# Main.net
KiCad netlist of a schematic drawn in EAGLE
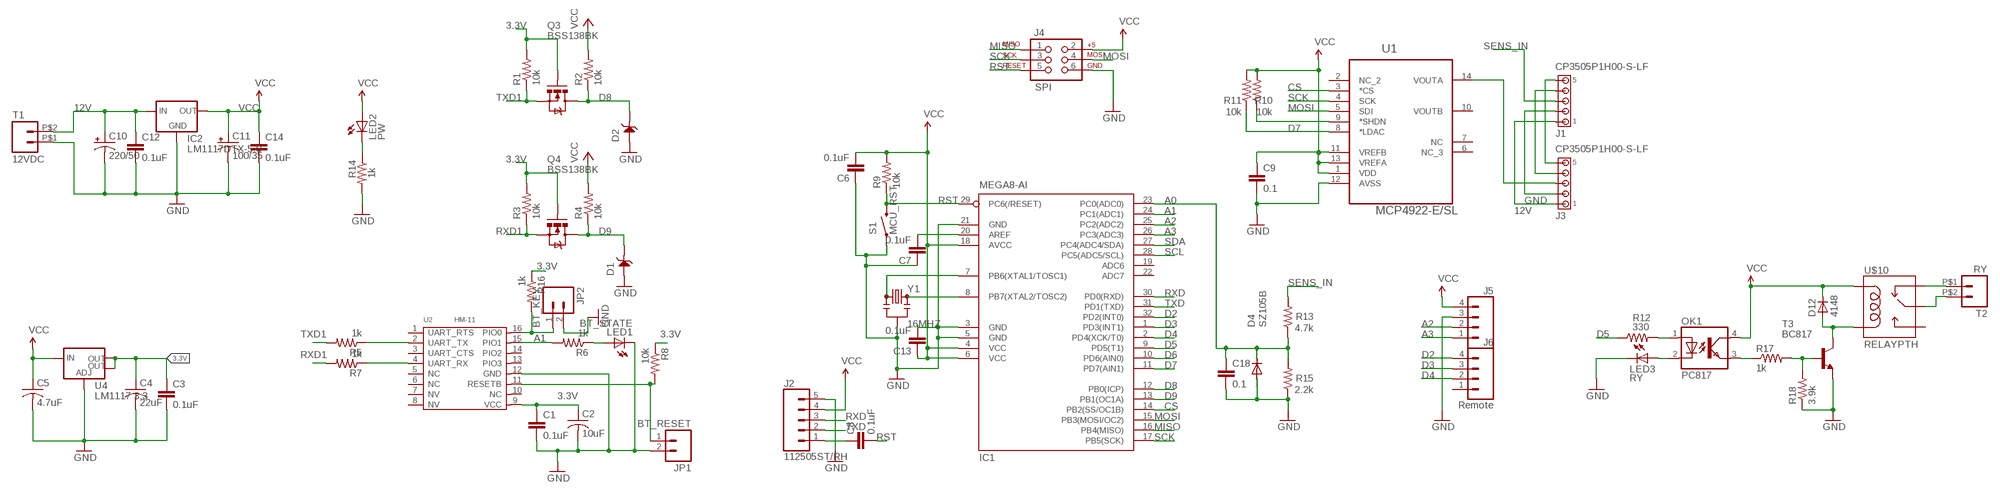
[diagram p0: schematic, sheet 1]

(export (version "E")
  (design (tool "Eeschema 10.0.6"))
  (components
    (comp (ref "C1")
      (value "0.1uF")
      (footprint "eagle-import:0805")
      (libsource (lib "eagle-import") (part "CAP0805"))
    )
    (comp (ref "C2")
      (value "10uF")
      (footprint "eagle-import:C1206")
      (libsource (lib "eagle-import") (part "C-USC1206"))
    )
    (comp (ref "C3")
      (value "0.1uF")
      (footprint "eagle-import:0805")
      (libsource (lib "eagle-import") (part "SparkFun-Passives_CAP0805"))
    )
    (comp (ref "C4")
      (value "22uF")
      (footprint "eagle-import:C1206")
      (libsource (lib "eagle-import") (part "C-USC1206"))
    )
    (comp (ref "C5")
      (value "4.7uF")
      (footprint "eagle-import:C1206")
      (libsource (lib "eagle-import") (part "C-USC1206"))
    )
    (comp (ref "C6")
      (value "0.1uF")
      (footprint "eagle-import:0805")
      (libsource (lib "eagle-import") (part "SparkFun-Passives_CAP0805"))
    )
    (comp (ref "C7")
      (value "0.1uF")
      (footprint "eagle-import:0805")
      (libsource (lib "eagle-import") (part "SparkFun-Passives_CAP0805"))
    )
    (comp (ref "C8")
      (value "0.1uF")
      (footprint "eagle-import:0805")
      (libsource (lib "eagle-import") (part "SparkFun-Passives_CAP0805"))
    )
    (comp (ref "C9")
      (value "0.1")
      (footprint "eagle-import:0805")
      (libsource (lib "eagle-import") (part "SparkFun-Passives_CAP0805"))
    )
    (comp (ref "C10")
      (value "220/50")
      (footprint "eagle-import:153CLV-1010")
      (libsource (lib "eagle-import") (part "CPOL-US153CLV-1010"))
    )
    (comp (ref "C11")
      (value "100/35")
      (footprint "eagle-import:153CLV-0605")
      (libsource (lib "eagle-import") (part "CPOL-US153CLV-0605"))
    )
    (comp (ref "C12")
      (value "0.1uF")
      (footprint "eagle-import:0805")
      (libsource (lib "eagle-import") (part "SparkFun-Passives_CAP0805"))
    )
    (comp (ref "C13")
      (value "0.1uF")
      (footprint "eagle-import:0805")
      (libsource (lib "eagle-import") (part "SparkFun-Passives_CAP0805"))
    )
    (comp (ref "C14")
      (value "0.1uF")
      (footprint "eagle-import:0805")
      (libsource (lib "eagle-import") (part "SparkFun-Passives_CAP0805"))
    )
    (comp (ref "C18")
      (value "0.1")
      (footprint "eagle-import:0805")
      (libsource (lib "eagle-import") (part "SparkFun-Passives_CAP0805"))
    )
    (comp (ref "D1")
      (value "SMF5.0A")
      (footprint "eagle-import:SOD123-2.7X1.6")
      (libsource (lib "eagle-import") (part "D-ESD-2P'CESD5V0D1'"))
    )
    (comp (ref "D2")
      (value "SMF5.0A")
      (footprint "eagle-import:SOD123-2.7X1.6")
      (libsource (lib "eagle-import") (part "D-ESD-2P'CESD5V0D1'"))
    )
    (comp (ref "D4")
      (value "SZ105B")
      (footprint "eagle-import:DO-214AC")
      (libsource (lib "eagle-import") (part "DIODE-DO-214AC"))
    )
    (comp (ref "D12")
      (value "4148")
      (footprint "eagle-import:SOD80")
      (libsource (lib "eagle-import") (part "D-SOD-80"))
    )
    (comp (ref "IC1")
      (value "MEGA8-AI")
      (footprint "eagle-import:TQFP32-08")
      (fields (field (name "MPN") "ATMEGA8-16AU"))
      (libsource (lib "eagle-import") (part "MEGA8-AI"))
    )
    (comp (ref "IC2")
      (value "LM1117DTX-5.0")
      (footprint "eagle-import:TO252")
      (libsource (lib "eagle-import") (part "LM1117DTX-3.3"))
    )
    (comp (ref "J1")
      (value "CP3505P1H00-S-LF")
      (footprint "eagle-import:1445055-5")
      (libsource (lib "eagle-import") (part "1445055-5"))
    )
    (comp (ref "J2")
      (value "112505ST/RH")
      (footprint "eagle-import:JST-5-PTH")
      (libsource (lib "eagle-import") (part "CONN_05JST"))
    )
    (comp (ref "J3")
      (value "CP3505P1H00-S-LF")
      (footprint "eagle-import:1445055-5")
      (libsource (lib "eagle-import") (part "1445055-5"))
    )
    (comp (ref "J4")
      (value "SPI")
      (footprint "eagle-import:2X3")
      (libsource (lib "eagle-import") (part "AVR_SPI_PRG_6PTH"))
    )
    (comp (ref "J5")
      (value "CONN_04JST-PTH")
      (footprint "eagle-import:JST-4-PTH")
      (libsource (lib "eagle-import") (part "CONN_04JST-PTH"))
    )
    (comp (ref "J6")
      (value "Remote")
      (footprint "eagle-import:JST-4-PTH")
      (libsource (lib "eagle-import") (part "CONN_04JST-PTH"))
    )
    (comp (ref "JP1")
      (value "BT_RESET")
      (footprint "eagle-import:1X02")
      (libsource (lib "eagle-import") (part "M02PTH"))
    )
    (comp (ref "JP2")
      (value "BT_KEY")
      (footprint "eagle-import:1X02")
      (libsource (lib "eagle-import") (part "M02PTH"))
    )
    (comp (ref "LED1")
      (value "BT_STATE")
      (footprint "eagle-import:LED3MM")
      (libsource (lib "eagle-import") (part "LED3MM"))
    )
    (comp (ref "LED2")
      (value "PW")
      (footprint "eagle-import:LED3MM")
      (libsource (lib "eagle-import") (part "LED3MM"))
    )
    (comp (ref "LED3")
      (value "RY")
      (footprint "eagle-import:LED3MM")
      (libsource (lib "eagle-import") (part "LED3MM"))
    )
    (comp (ref "OK1")
      (value "PC817")
      (footprint "eagle-import:DIL4-SMD")
      (libsource (lib "eagle-import") (part "LTV816S"))
    )
    (comp (ref "Q3")
      (value "BSS138BK")
      (footprint "eagle-import:SOT23-3")
      (libsource (lib "eagle-import") (part "MOSFET-NCHANNELBSS138"))
    )
    (comp (ref "Q4")
      (value "BSS138BK")
      (footprint "eagle-import:SOT23-3")
      (libsource (lib "eagle-import") (part "MOSFET-NCHANNELBSS138"))
    )
    (comp (ref "R1")
      (value "10k")
      (footprint "eagle-import:0805")
      (libsource (lib "eagle-import") (part "SparkFun-Resistors_RESISTOR0805-RES"))
    )
    (comp (ref "R2")
      (value "10k")
      (footprint "eagle-import:0805")
      (libsource (lib "eagle-import") (part "SparkFun-Resistors_RESISTOR0805-RES"))
    )
    (comp (ref "R3")
      (value "10k")
      (footprint "eagle-import:0805")
      (libsource (lib "eagle-import") (part "SparkFun-Resistors_RESISTOR0805-RES"))
    )
    (comp (ref "R4")
      (value "10k")
      (footprint "eagle-import:0805")
      (libsource (lib "eagle-import") (part "SparkFun-Resistors_RESISTOR0805-RES"))
    )
    (comp (ref "R5")
      (value "1k")
      (footprint "eagle-import:0805")
      (libsource (lib "eagle-import") (part "SparkFun-Resistors_RESISTOR0805-RES"))
    )
    (comp (ref "R6")
      (value "1k")
      (footprint "eagle-import:0805")
      (libsource (lib "eagle-import") (part "SparkFun-Resistors_RESISTOR0805-RES"))
    )
    (comp (ref "R7")
      (value "1k")
      (footprint "eagle-import:0805")
      (libsource (lib "eagle-import") (part "SparkFun-Resistors_RESISTOR0805-RES"))
    )
    (comp (ref "R8")
      (value "10k")
      (footprint "eagle-import:0805")
      (libsource (lib "eagle-import") (part "SparkFun-Resistors_RESISTOR0805-RES"))
    )
    (comp (ref "R9")
      (value "10k")
      (footprint "eagle-import:0805")
      (libsource (lib "eagle-import") (part "SparkFun-Resistors_RESISTOR0805-RES"))
    )
    (comp (ref "R10")
      (value "10k")
      (footprint "eagle-import:0805")
      (libsource (lib "eagle-import") (part "SparkFun-Resistors_RESISTOR0805-RES"))
    )
    (comp (ref "R11")
      (value "10k")
      (footprint "eagle-import:0805")
      (libsource (lib "eagle-import") (part "SparkFun-Resistors_RESISTOR0805-RES"))
    )
    (comp (ref "R12")
      (value "330")
      (footprint "eagle-import:0805")
      (libsource (lib "eagle-import") (part "RESISTOR0805-RES"))
    )
    (comp (ref "R13")
      (value "4.7k")
      (footprint "eagle-import:0805")
      (libsource (lib "eagle-import") (part "SparkFun-Resistors_RESISTOR0805-RES"))
    )
    (comp (ref "R14")
      (value "1k")
      (footprint "eagle-import:0805")
      (libsource (lib "eagle-import") (part "SparkFun-Resistors_RESISTOR0805-RES"))
    )
    (comp (ref "R15")
      (value "2.2k")
      (footprint "eagle-import:0805")
      (libsource (lib "eagle-import") (part "SparkFun-Resistors_RESISTOR0805-RES"))
    )
    (comp (ref "R16")
      (value "1k")
      (footprint "eagle-import:0805")
      (libsource (lib "eagle-import") (part "SparkFun-Resistors_RESISTOR0805-RES"))
    )
    (comp (ref "R17")
      (value "1k")
      (footprint "eagle-import:0805")
      (libsource (lib "eagle-import") (part "RESISTOR0805-RES"))
    )
    (comp (ref "R18")
      (value "3.9k")
      (footprint "eagle-import:0805")
      (libsource (lib "eagle-import") (part "RESISTOR0805-RES"))
    )
    (comp (ref "S1")
      (value "MCU_RST")
      (footprint "eagle-import:TACTILE-SWITCH-1101NE")
      (libsource (lib "eagle-import") (part "SWITCH-MOMENTARY-2SMD-1101NE"))
    )
    (comp (ref "T1")
      (value "12VDC")
      (footprint "eagle-import:ED350V-02P")
      (libsource (lib "eagle-import") (part "ST02-3.5MM"))
    )
    (comp (ref "T2")
      (value "RY")
      (footprint "eagle-import:ED350V-02P")
      (libsource (lib "eagle-import") (part "ST02-3.5MM"))
    )
    (comp (ref "T3")
      (value "BC817")
      (footprint "eagle-import:SOT23-BEC")
      (libsource (lib "eagle-import") (part "-NPN-SOT23-BECBC817-16"))
    )
    (comp (ref "U$10")
      (value "RELAYPTH")
      (footprint "eagle-import:SRD-05VDC-SL-C")
      (libsource (lib "eagle-import") (part "RELAYPTH"))
    )
    (comp (ref "U1")
      (value "MCP4922-E/SL")
      (footprint "eagle-import:SOIC127P600X175-14N")
      (libsource (lib "eagle-import") (part "MCP4922-E/SL"))
    )
    (comp (ref "U2")
      (value "HM-11")
      (footprint "eagle-import:16P-18.5X13.5X0.8")
      (libsource (lib "eagle-import") (part "HM-11"))
    )
    (comp (ref "U4")
      (value "LM1117 3.3")
      (footprint "eagle-import:SOT223")
      (libsource (lib "eagle-import") (part "V_REG_LM1117SOT223"))
    )
    (comp (ref "Y1")
      (value "16MHZ")
      (footprint "eagle-import:RESONATOR-SMD")
      (libsource (lib "eagle-import") (part "RESONATOR16MHZ"))
    )
  )
  (nets
    (net (code "1") (name "/12V") (class "Default")
      (node (ref "C10") (pin "+") (pinfunction "+_+") (pintype "passive"))
      (node (ref "C12") (pin "1") (pinfunction "1_1") (pintype "passive"))
      (node (ref "IC2") (pin "2") (pinfunction "IN_2") (pintype "input"))
      (node (ref "J1") (pin "1") (pinfunction "1_1") (pintype "passive"))
      (node (ref "J3") (pin "1") (pinfunction "1_1") (pintype "passive"))
      (node (ref "T1") (pin "P$2") (pinfunction "2_P$2") (pintype "passive"))
    )
    (net (code "2") (name "/A0") (class "Default")
      (node (ref "C18") (pin "1") (pinfunction "1_1") (pintype "passive"))
      (node (ref "D4") (pin "C") (pinfunction "C_C") (pintype "passive"))
      (node (ref "IC1") (pin "23") (pinfunction "PC0(ADC0)_23") (pintype "bidirectional"))
      (node (ref "R13") (pin "1") (pinfunction "1_1") (pintype "passive"))
      (node (ref "R15") (pin "2") (pinfunction "2_2") (pintype "passive"))
    )
    (net (code "3") (name "/A1") (class "Default")
      (node (ref "IC1") (pin "24") (pinfunction "PC1(ADC1)_24") (pintype "bidirectional"))
      (node (ref "R6") (pin "2") (pinfunction "2_2") (pintype "passive"))
      (node (ref "U2") (pin "15") (pinfunction "PIO1_15") (pintype "bidirectional"))
    )
    (net (code "4") (name "/A2") (class "Default")
      (node (ref "IC1") (pin "25") (pinfunction "PC2(ADC2)_25") (pintype "bidirectional"))
      (node (ref "J5") (pin "2") (pinfunction "2_2") (pintype "passive"))
    )
    (net (code "5") (name "/A3") (class "Default")
      (node (ref "IC1") (pin "26") (pinfunction "PC3(ADC3)_26") (pintype "bidirectional"))
      (node (ref "J5") (pin "1") (pinfunction "1_1") (pintype "passive"))
    )
    (net (code "6") (name "/CS") (class "Default")
      (node (ref "IC1") (pin "14") (pinfunction "PB2(SS/OC1B)_14") (pintype "bidirectional"))
      (node (ref "U1") (pin "3") (pinfunction "*CS_3") (pintype "input"))
    )
    (net (code "7") (name "/D2") (class "Default")
      (node (ref "IC1") (pin "32") (pinfunction "PD2(INT0)_32") (pintype "bidirectional"))
      (node (ref "J6") (pin "4") (pinfunction "4_4") (pintype "passive"))
    )
    (net (code "8") (name "/D3") (class "Default")
      (node (ref "IC1") (pin "1") (pinfunction "PD3(INT1)_1") (pintype "bidirectional"))
      (node (ref "J6") (pin "3") (pinfunction "3_3") (pintype "passive"))
    )
    (net (code "9") (name "/D4") (class "Default")
      (node (ref "IC1") (pin "2") (pinfunction "PD4(XCK/T0)_2") (pintype "bidirectional"))
      (node (ref "J6") (pin "2") (pinfunction "2_2") (pintype "passive"))
    )
    (net (code "10") (name "/D5") (class "Default")
      (node (ref "IC1") (pin "9") (pinfunction "PD5(T1)_9") (pintype "bidirectional"))
      (node (ref "R12") (pin "1") (pinfunction "1_1") (pintype "passive"))
    )
    (net (code "11") (name "/D6") (class "Default")
      (node (ref "IC1") (pin "10") (pinfunction "PD6(AIN0)_10") (pintype "bidirectional"))
    )
    (net (code "12") (name "/D7") (class "Default")
      (node (ref "IC1") (pin "11") (pinfunction "PD7(AIN1)_11") (pintype "bidirectional"))
      (node (ref "R11") (pin "1") (pinfunction "1_1") (pintype "passive"))
      (node (ref "U1") (pin "8") (pinfunction "*LDAC_8") (pintype "input"))
    )
    (net (code "13") (name "/D8") (class "Default")
      (node (ref "D2") (pin "2") (pinfunction "2_2") (pintype "bidirectional"))
      (node (ref "IC1") (pin "12") (pinfunction "PB0(ICP)_12") (pintype "bidirectional"))
      (node (ref "Q3") (pin "3") (pinfunction "D_3") (pintype "passive"))
      (node (ref "R2") (pin "1") (pinfunction "1_1") (pintype "passive"))
    )
    (net (code "14") (name "/D9") (class "Default")
      (node (ref "D1") (pin "2") (pinfunction "2_2") (pintype "bidirectional"))
      (node (ref "IC1") (pin "13") (pinfunction "PB1(OC1A)_13") (pintype "bidirectional"))
      (node (ref "Q4") (pin "3") (pinfunction "D_3") (pintype "passive"))
      (node (ref "R4") (pin "1") (pinfunction "1_1") (pintype "passive"))
    )
    (net (code "15") (name "/MISO") (class "Default")
      (node (ref "IC1") (pin "16") (pinfunction "PB4(MISO)_16") (pintype "bidirectional"))
      (node (ref "J4") (pin "1") (pinfunction "1_1") (pintype "passive"))
    )
    (net (code "16") (name "/MOSI") (class "Default")
      (node (ref "IC1") (pin "15") (pinfunction "PB3(MOSI/OC2)_15") (pintype "bidirectional"))
      (node (ref "J4") (pin "4") (pinfunction "4_4") (pintype "passive"))
      (node (ref "U1") (pin "5") (pinfunction "SDI_5") (pintype "input"))
    )
    (net (code "17") (name "/RST") (class "Default")
      (node (ref "C8") (pin "2") (pinfunction "2_2") (pintype "passive"))
      (node (ref "IC1") (pin "29") (pinfunction "PC6(/RESET)_29") (pintype "bidirectional"))
      (node (ref "J4") (pin "5") (pinfunction "5_5") (pintype "passive"))
      (node (ref "R9") (pin "1") (pinfunction "1_1") (pintype "passive"))
      (node (ref "S1") (pin "2") (pinfunction "2_2") (pintype "passive"))
    )
    (net (code "18") (name "/RXD") (class "Default")
      (node (ref "IC1") (pin "30") (pinfunction "PD0(RXD)_30") (pintype "bidirectional"))
      (node (ref "J2") (pin "3") (pinfunction "3_3") (pintype "passive"))
    )
    (net (code "19") (name "/RXD1") (class "Default")
      (node (ref "Q4") (pin "2") (pinfunction "S_2") (pintype "passive"))
      (node (ref "R3") (pin "1") (pinfunction "1_1") (pintype "passive"))
      (node (ref "R7") (pin "2") (pinfunction "2_2") (pintype "passive"))
    )
    (net (code "20") (name "/SCK") (class "Default")
      (node (ref "IC1") (pin "17") (pinfunction "PB5(SCK)_17") (pintype "bidirectional"))
      (node (ref "J4") (pin "3") (pinfunction "3_3") (pintype "passive"))
      (node (ref "U1") (pin "4") (pinfunction "SCK_4") (pintype "input"))
    )
    (net (code "21") (name "/SCL") (class "Default")
      (node (ref "IC1") (pin "28") (pinfunction "PC5(ADC5/SCL)_28") (pintype "bidirectional"))
    )
    (net (code "22") (name "/SDA") (class "Default")
      (node (ref "IC1") (pin "27") (pinfunction "PC4(ADC4/SDA)_27") (pintype "bidirectional"))
    )
    (net (code "23") (name "/SENS_IN") (class "Default")
      (node (ref "J1") (pin "3") (pinfunction "3_3") (pintype "passive"))
      (node (ref "R13") (pin "2") (pinfunction "2_2") (pintype "passive"))
    )
    (net (code "24") (name "/TXD") (class "Default")
      (node (ref "IC1") (pin "31") (pinfunction "PD1(TXD)_31") (pintype "bidirectional"))
      (node (ref "J2") (pin "2") (pinfunction "2_2") (pintype "passive"))
    )
    (net (code "25") (name "/TXD1") (class "Default")
      (node (ref "Q3") (pin "2") (pinfunction "S_2") (pintype "passive"))
      (node (ref "R1") (pin "1") (pinfunction "1_1") (pintype "passive"))
      (node (ref "R5") (pin "2") (pinfunction "2_2") (pintype "passive"))
    )
    (net (code "26") (name "3.3V") (class "Default")
      (node (ref "C1") (pin "1") (pinfunction "1_1") (pintype "passive"))
      (node (ref "C2") (pin "1") (pinfunction "1_1") (pintype "passive"))
      (node (ref "C3") (pin "1") (pinfunction "1_1") (pintype "passive"))
      (node (ref "C4") (pin "1") (pinfunction "1_1") (pintype "passive"))
      (node (ref "Q3") (pin "1") (pinfunction "G_1") (pintype "passive"))
      (node (ref "Q4") (pin "1") (pinfunction "G_1") (pintype "passive"))
      (node (ref "R1") (pin "2") (pinfunction "2_2") (pintype "passive"))
      (node (ref "R16") (pin "1") (pinfunction "1_1") (pintype "passive"))
      (node (ref "R3") (pin "2") (pinfunction "2_2") (pintype "passive"))
      (node (ref "R8") (pin "1") (pinfunction "1_1") (pintype "passive"))
      (node (ref "U2") (pin "9") (pinfunction "VCC_9") (pintype "bidirectional"))
      (node (ref "U4") (pin "2") (pinfunction "OUT_2") (pintype "output"))
      (node (ref "U4") (pin "4") (pinfunction "OUT_4") (pintype "output"))
    )
    (net (code "27") (name "GND") (class "Default")
      (node (ref "C1") (pin "2") (pinfunction "2_2") (pintype "passive"))
      (node (ref "C10") (pin "-") (pinfunction "-_-") (pintype "passive"))
      (node (ref "C11") (pin "-") (pinfunction "-_-") (pintype "passive"))
      (node (ref "C12") (pin "2") (pinfunction "2_2") (pintype "passive"))
      (node (ref "C13") (pin "2") (pinfunction "2_2") (pintype "passive"))
      (node (ref "C14") (pin "2") (pinfunction "2_2") (pintype "passive"))
      (node (ref "C18") (pin "2") (pinfunction "2_2") (pintype "passive"))
      (node (ref "C2") (pin "2") (pinfunction "2_2") (pintype "passive"))
      (node (ref "C3") (pin "2") (pinfunction "2_2") (pintype "passive"))
      (node (ref "C4") (pin "2") (pinfunction "2_2") (pintype "passive"))
      (node (ref "C5") (pin "2") (pinfunction "2_2") (pintype "passive"))
      (node (ref "C6") (pin "1") (pinfunction "1_1") (pintype "passive"))
      (node (ref "C7") (pin "1") (pinfunction "1_1") (pintype "passive"))
      (node (ref "C9") (pin "2") (pinfunction "2_2") (pintype "passive"))
      (node (ref "D1") (pin "1") (pinfunction "1_1") (pintype "bidirectional"))
      (node (ref "D2") (pin "1") (pinfunction "1_1") (pintype "bidirectional"))
      (node (ref "D4") (pin "A") (pinfunction "A_A") (pintype "passive"))
      (node (ref "IC1") (pin "21") (pinfunction "GND_21") (pintype "power_in"))
      (node (ref "IC1") (pin "3") (pinfunction "GND_3") (pintype "power_in"))
      (node (ref "IC1") (pin "5") (pinfunction "GND_5") (pintype "power_in"))
      (node (ref "IC2") (pin "1") (pinfunction "GND_1") (pintype "input"))
      (node (ref "J1") (pin "2") (pinfunction "2_2") (pintype "passive"))
      (node (ref "J2") (pin "5") (pinfunction "5_5") (pintype "passive"))
      (node (ref "J3") (pin "2") (pinfunction "2_2") (pintype "passive"))
      (node (ref "J4") (pin "6") (pinfunction "6_6") (pintype "passive"))
      (node (ref "J5") (pin "3") (pinfunction "3_3") (pintype "passive"))
      (node (ref "JP1") (pin "2") (pinfunction "2_2") (pintype "passive"))
      (node (ref "JP2") (pin "2") (pinfunction "2_2") (pintype "passive"))
      (node (ref "LED1") (pin "K") (pinfunction "C_K") (pintype "passive"))
      (node (ref "LED3") (pin "K") (pinfunction "C_K") (pintype "passive"))
      (node (ref "R14") (pin "2") (pinfunction "2_2") (pintype "passive"))
      (node (ref "R15") (pin "1") (pinfunction "1_1") (pintype "passive"))
      (node (ref "R18") (pin "1") (pinfunction "1_1") (pintype "passive"))
      (node (ref "S1") (pin "1") (pinfunction "1_1") (pintype "passive"))
      (node (ref "T1") (pin "P$1") (pinfunction "1_P$1") (pintype "passive"))
      (node (ref "T3") (pin "E") (pinfunction "E_E") (pintype "passive"))
      (node (ref "U1") (pin "12") (pinfunction "AVSS_12") (pintype "passive"))
      (node (ref "U2") (pin "12") (pinfunction "GND_12") (pintype "bidirectional"))
      (node (ref "U4") (pin "1") (pinfunction "ADJ_1") (pintype "input"))
      (node (ref "Y1") (pin "2") (pinfunction "2_2") (pintype "passive"))
    )
    (net (code "28") (name "Net-(C8-Pad1)") (class "Default")
      (node (ref "C8") (pin "1") (pinfunction "1_1") (pintype "passive"))
      (node (ref "J2") (pin "1") (pinfunction "1_1") (pintype "passive"))
    )
    (net (code "29") (name "Net-(D12-A)") (class "Default")
      (node (ref "D12") (pin "2") (pinfunction "A_2") (pintype "passive"))
      (node (ref "T3") (pin "C") (pinfunction "C_C") (pintype "passive"))
      (node (ref "U$10") (pin "COIL0") (pinfunction "COIL0_COIL0") (pintype "bidirectional"))
    )
    (net (code "30") (name "Net-(IC1-AREF)") (class "Default")
      (node (ref "C7") (pin "2") (pinfunction "2_2") (pintype "passive"))
      (node (ref "IC1") (pin "20") (pinfunction "AREF_20") (pintype "passive"))
    )
    (net (code "31") (name "Net-(IC1-PB6(XTAL1{slash}TOSC1))") (class "Default")
      (node (ref "IC1") (pin "7") (pinfunction "PB6(XTAL1/TOSC1)_7") (pintype "bidirectional"))
      (node (ref "Y1") (pin "1") (pinfunction "1_1") (pintype "passive"))
    )
    (net (code "32") (name "Net-(IC1-PB7(XTAL2{slash}TOSC2))") (class "Default")
      (node (ref "IC1") (pin "8") (pinfunction "PB7(XTAL2/TOSC2)_8") (pintype "bidirectional"))
      (node (ref "Y1") (pin "3") (pinfunction "3_3") (pintype "passive"))
    )
    (net (code "33") (name "Net-(J1-Pad4)") (class "Default")
      (node (ref "J1") (pin "4") (pinfunction "4_4") (pintype "passive"))
      (node (ref "J3") (pin "4") (pinfunction "4_4") (pintype "passive"))
    )
    (net (code "34") (name "Net-(J1-Pad5)") (class "Default")
      (node (ref "J1") (pin "5") (pinfunction "5_5") (pintype "passive"))
      (node (ref "J3") (pin "5") (pinfunction "5_5") (pintype "passive"))
    )
    (net (code "35") (name "Net-(LED1-PadA)") (class "Default")
      (node (ref "LED1") (pin "A") (pinfunction "A_A") (pintype "passive"))
      (node (ref "R6") (pin "1") (pinfunction "1_1") (pintype "passive"))
    )
    (net (code "36") (name "Net-(LED2-C)") (class "Default")
      (node (ref "LED2") (pin "K") (pinfunction "C_K") (pintype "passive"))
      (node (ref "R14") (pin "1") (pinfunction "1_1") (pintype "passive"))
    )
    (net (code "37") (name "Net-(OK1-A)") (class "Default")
      (node (ref "OK1") (pin "1") (pinfunction "A_1") (pintype "passive"))
      (node (ref "R12") (pin "2") (pinfunction "2_2") (pintype "passive"))
    )
    (net (code "38") (name "Net-(OK1-C)") (class "Default")
      (node (ref "LED3") (pin "A") (pinfunction "A_A") (pintype "passive"))
      (node (ref "OK1") (pin "2") (pinfunction "C_2") (pintype "passive"))
    )
    (net (code "39") (name "Net-(OK1-EMIT)") (class "Default")
      (node (ref "OK1") (pin "3") (pinfunction "EMIT_3") (pintype "passive"))
      (node (ref "R17") (pin "1") (pinfunction "1_1") (pintype "passive"))
    )
    (net (code "40") (name "Net-(R17-Pad2)") (class "Default")
      (node (ref "R17") (pin "2") (pinfunction "2_2") (pintype "passive"))
      (node (ref "R18") (pin "2") (pinfunction "2_2") (pintype "passive"))
      (node (ref "T3") (pin "B") (pinfunction "B_B") (pintype "passive"))
    )
    (net (code "41") (name "Net-(T2-1)") (class "Default")
      (node (ref "T2") (pin "P$1") (pinfunction "1_P$1") (pintype "passive"))
      (node (ref "U$10") (pin "SWCLOSED") (pinfunction "SWCLOSE_SWCLOSED") (pintype "bidirectional"))
    )
    (net (code "42") (name "Net-(T2-2)") (class "Default")
      (node (ref "T2") (pin "P$2") (pinfunction "2_P$2") (pintype "passive"))
      (node (ref "U$10") (pin "SWCOMMON") (pinfunction "SWCOMMON_SWCOMMON") (pintype "bidirectional"))
    )
    (net (code "43") (name "Net-(U1-*SHDN)") (class "Default")
      (node (ref "R10") (pin "1") (pinfunction "1_1") (pintype "passive"))
      (node (ref "U1") (pin "9") (pinfunction "*SHDN_9") (pintype "input"))
    )
    (net (code "44") (name "Net-(U1-VOUTA)") (class "Default")
      (node (ref "J3") (pin "3") (pinfunction "3_3") (pintype "passive"))
      (node (ref "U1") (pin "14") (pinfunction "VOUTA_14") (pintype "output"))
    )
    (net (code "45") (name "Net-(U2-PIO0)") (class "Default")
      (node (ref "JP2") (pin "1") (pinfunction "1_1") (pintype "passive"))
      (node (ref "R16") (pin "2") (pinfunction "2_2") (pintype "passive"))
      (node (ref "U2") (pin "16") (pinfunction "PIO0_16") (pintype "bidirectional"))
    )
    (net (code "46") (name "Net-(U2-RESETB)") (class "Default")
      (node (ref "JP1") (pin "1") (pinfunction "1_1") (pintype "passive"))
      (node (ref "R8") (pin "2") (pinfunction "2_2") (pintype "passive"))
      (node (ref "U2") (pin "11") (pinfunction "RESETB_11") (pintype "bidirectional"))
    )
    (net (code "47") (name "Net-(U2-UART_RX)") (class "Default")
      (node (ref "R7") (pin "1") (pinfunction "1_1") (pintype "passive"))
      (node (ref "U2") (pin "4") (pinfunction "UART_RX_4") (pintype "bidirectional"))
    )
    (net (code "48") (name "Net-(U2-UART_TX)") (class "Default")
      (node (ref "R5") (pin "1") (pinfunction "1_1") (pintype "passive"))
      (node (ref "U2") (pin "2") (pinfunction "UART_TX_2") (pintype "bidirectional"))
    )
    (net (code "49") (name "VCC") (class "Default")
      (node (ref "C11") (pin "+") (pinfunction "+_+") (pintype "passive"))
      (node (ref "C13") (pin "1") (pinfunction "1_1") (pintype "passive"))
      (node (ref "C14") (pin "1") (pinfunction "1_1") (pintype "passive"))
      (node (ref "C5") (pin "1") (pinfunction "1_1") (pintype "passive"))
      (node (ref "C6") (pin "2") (pinfunction "2_2") (pintype "passive"))
      (node (ref "C9") (pin "1") (pinfunction "1_1") (pintype "passive"))
      (node (ref "D12") (pin "1") (pinfunction "C_1") (pintype "passive"))
      (node (ref "IC1") (pin "18") (pinfunction "AVCC_18") (pintype "power_in"))
      (node (ref "IC1") (pin "4") (pinfunction "VCC_4") (pintype "power_in"))
      (node (ref "IC1") (pin "6") (pinfunction "VCC_6") (pintype "power_in"))
      (node (ref "IC2") (pin "TAB") (pinfunction "OUT_TAB") (pintype "passive"))
      (node (ref "J2") (pin "4") (pinfunction "4_4") (pintype "passive"))
      (node (ref "J4") (pin "2") (pinfunction "2_2") (pintype "passive"))
      (node (ref "J5") (pin "4") (pinfunction "4_4") (pintype "passive"))
      (node (ref "LED2") (pin "A") (pinfunction "A_A") (pintype "passive"))
      (node (ref "OK1") (pin "4") (pinfunction "COL_4") (pintype "passive"))
      (node (ref "R10") (pin "2") (pinfunction "2_2") (pintype "passive"))
      (node (ref "R11") (pin "2") (pinfunction "2_2") (pintype "passive"))
      (node (ref "R2") (pin "2") (pinfunction "2_2") (pintype "passive"))
      (node (ref "R4") (pin "2") (pinfunction "2_2") (pintype "passive"))
      (node (ref "R9") (pin "2") (pinfunction "2_2") (pintype "passive"))
      (node (ref "U$10") (pin "COIL1") (pinfunction "COIL1_COIL1") (pintype "bidirectional"))
      (node (ref "U1") (pin "1") (pinfunction "VDD_1") (pintype "power_in"))
      (node (ref "U1") (pin "11") (pinfunction "VREFB_11") (pintype "input"))
      (node (ref "U1") (pin "13") (pinfunction "VREFA_13") (pintype "input"))
      (node (ref "U4") (pin "3") (pinfunction "IN_3") (pintype "input"))
    )
    (net (code "50") (name "unconnected-(IC1-ADC6-Pad19)") (class "Default")
      (node (ref "IC1") (pin "19") (pinfunction "ADC6_19") (pintype "bidirectional"))
    )
    (net (code "51") (name "unconnected-(IC1-ADC7-Pad22)") (class "Default")
      (node (ref "IC1") (pin "22") (pinfunction "ADC7_22") (pintype "bidirectional"))
    )
    (net (code "52") (name "unconnected-(J6-Pad1)") (class "Default")
      (node (ref "J6") (pin "1") (pinfunction "1_1") (pintype "passive"))
    )
    (net (code "53") (name "unconnected-(U$10-PadSWOPEN)") (class "Default")
      (node (ref "U$10") (pin "SWOPEN") (pinfunction "SWOPEN_SWOPEN") (pintype "bidirectional"))
    )
    (net (code "54") (name "unconnected-(U1-NC-Pad7)") (class "Default")
      (node (ref "U1") (pin "7") (pinfunction "NC_7") (pintype "no_connect"))
    )
    (net (code "55") (name "unconnected-(U1-NC_2-Pad2)") (class "Default")
      (node (ref "U1") (pin "2") (pinfunction "NC_2_2") (pintype "no_connect"))
    )
    (net (code "56") (name "unconnected-(U1-NC_3-Pad6)") (class "Default")
      (node (ref "U1") (pin "6") (pinfunction "NC_3_6") (pintype "no_connect"))
    )
    (net (code "57") (name "unconnected-(U1-VOUTB-Pad10)") (class "Default")
      (node (ref "U1") (pin "10") (pinfunction "VOUTB_10") (pintype "output"))
    )
    (net (code "58") (name "unconnected-(U2-NC-Pad5)") (class "Default")
      (node (ref "U2") (pin "5") (pinfunction "NC_5") (pintype "bidirectional"))
    )
    (net (code "59") (name "unconnected-(U2-NC-Pad6)") (class "Default")
      (node (ref "U2") (pin "6") (pinfunction "NC_6") (pintype "bidirectional"))
    )
    (net (code "60") (name "unconnected-(U2-NC-Pad10)") (class "Default")
      (node (ref "U2") (pin "10") (pinfunction "NC_10") (pintype "bidirectional"))
    )
    (net (code "61") (name "unconnected-(U2-NV-Pad7)") (class "Default")
      (node (ref "U2") (pin "7") (pinfunction "NV_7") (pintype "bidirectional"))
    )
    (net (code "62") (name "unconnected-(U2-NV-Pad8)") (class "Default")
      (node (ref "U2") (pin "8") (pinfunction "NV_8") (pintype "bidirectional"))
    )
    (net (code "63") (name "unconnected-(U2-PIO2-Pad14)") (class "Default")
      (node (ref "U2") (pin "14") (pinfunction "PIO2_14") (pintype "bidirectional"))
    )
    (net (code "64") (name "unconnected-(U2-PIO3-Pad13)") (class "Default")
      (node (ref "U2") (pin "13") (pinfunction "PIO3_13") (pintype "bidirectional"))
    )
    (net (code "65") (name "unconnected-(U2-UART_CTS-Pad3)") (class "Default")
      (node (ref "U2") (pin "3") (pinfunction "UART_CTS_3") (pintype "bidirectional"))
    )
    (net (code "66") (name "unconnected-(U2-UART_RTS-Pad1)") (class "Default")
      (node (ref "U2") (pin "1") (pinfunction "UART_RTS_1") (pintype "bidirectional"))
    )
  )
)
